# SparkIO_Thermal_Shield.net
KiCad netlist of a schematic drawn in Altium Designer
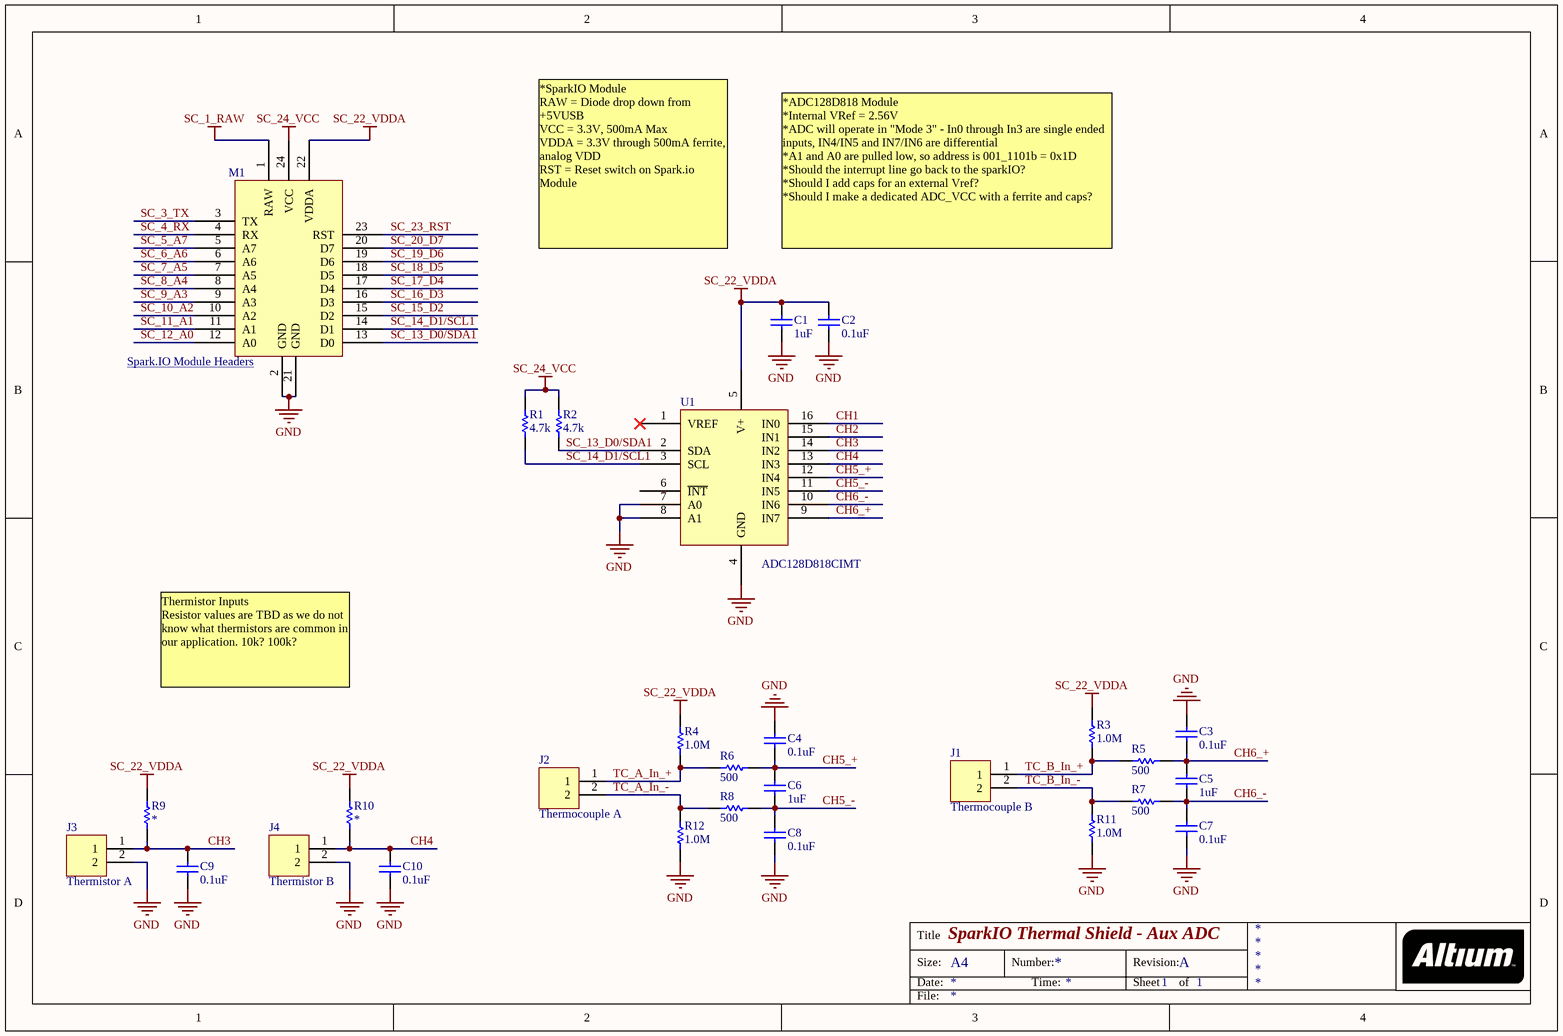
[diagram p0: SparkIO Thermal Shield.SchDoc]

(export (version "E")
  (design (tool "Eeschema 10.0.6"))
  (components
    (comp (ref "C1")
      (value "1uF")
      (footprint "0603")
      (description "Capacitor")
      (libsource (lib "MakerBot") (part "Capacitor"))
    )
    (comp (ref "C2")
      (value "0.1uF")
      (footprint "0603")
      (description "Capacitor")
      (libsource (lib "MakerBot") (part "Capacitor"))
    )
    (comp (ref "C3")
      (value "0.1uF")
      (footprint "0603")
      (description "Capacitor")
      (libsource (lib "MakerBot") (part "Capacitor"))
    )
    (comp (ref "C4")
      (value "0.1uF")
      (footprint "0603")
      (description "Capacitor")
      (libsource (lib "MakerBot") (part "Capacitor"))
    )
    (comp (ref "C5")
      (value "1uF")
      (footprint "0603")
      (description "Capacitor")
      (libsource (lib "MakerBot") (part "Capacitor"))
    )
    (comp (ref "C6")
      (value "1uF")
      (footprint "0603")
      (description "Capacitor")
      (libsource (lib "MakerBot") (part "Capacitor"))
    )
    (comp (ref "C7")
      (value "0.1uF")
      (footprint "0603")
      (description "Capacitor")
      (libsource (lib "MakerBot") (part "Capacitor"))
    )
    (comp (ref "C8")
      (value "0.1uF")
      (footprint "0603")
      (description "Capacitor")
      (libsource (lib "MakerBot") (part "Capacitor"))
    )
    (comp (ref "C9")
      (value "0.1uF")
      (footprint "0603")
      (description "Capacitor")
      (libsource (lib "MakerBot") (part "Capacitor"))
    )
    (comp (ref "C10")
      (value "0.1uF")
      (footprint "0603")
      (description "Capacitor")
      (libsource (lib "MakerBot") (part "Capacitor"))
    )
    (comp (ref "J1")
      (value "Thermocouple B")
      (footprint "HDR1X2")
      (description "Header .1\" 2 Pos")
      (libsource (lib "MakerBot") (part "Header 2"))
    )
    (comp (ref "J2")
      (value "Thermocouple A")
      (footprint "HDR1X2")
      (description "Header .1\" 2 Pos")
      (libsource (lib "MakerBot") (part "Header 2"))
    )
    (comp (ref "J3")
      (value "Thermistor A")
      (footprint "HDR1X2")
      (description "Header .1\" 2 Pos")
      (libsource (lib "MakerBot") (part "Header 2"))
    )
    (comp (ref "J4")
      (value "Thermistor B")
      (footprint "HDR1X2")
      (description "Header .1\" 2 Pos")
      (libsource (lib "MakerBot") (part "Header 2"))
    )
    (comp (ref "M1")
      (value "Spark.IO Module Headers")
      (description "SparkIO Module Interface Headers")
      (libsource (lib "MakerBot") (part "SparkIO Module Interface"))
    )
    (comp (ref "R1")
      (value "4.7k")
      (footprint "0603")
      (description "Resistor")
      (libsource (lib "MakerBot") (part "Resistor"))
    )
    (comp (ref "R2")
      (value "4.7k")
      (footprint "0603")
      (description "Resistor")
      (libsource (lib "MakerBot") (part "Resistor"))
    )
    (comp (ref "R3")
      (value "1.0M")
      (footprint "0603")
      (description "Resistor")
      (libsource (lib "MakerBot") (part "Resistor"))
    )
    (comp (ref "R4")
      (value "1.0M")
      (footprint "0603")
      (description "Resistor")
      (libsource (lib "MakerBot") (part "Resistor"))
    )
    (comp (ref "R5")
      (value "500")
      (footprint "0603")
      (description "Resistor")
      (libsource (lib "MakerBot") (part "Resistor"))
    )
    (comp (ref "R6")
      (value "500")
      (footprint "0603")
      (description "Resistor")
      (libsource (lib "MakerBot") (part "Resistor"))
    )
    (comp (ref "R7")
      (value "500")
      (footprint "0603")
      (description "Resistor")
      (libsource (lib "MakerBot") (part "Resistor"))
    )
    (comp (ref "R8")
      (value "500")
      (footprint "0603")
      (description "Resistor")
      (libsource (lib "MakerBot") (part "Resistor"))
    )
    (comp (ref "R9")
      (value "Resistor")
      (footprint "0603")
      (fields (field (name "ALTIUM_VALUE") "*"))
      (libsource (lib "MakerBot") (part "Resistor"))
    )
    (comp (ref "R10")
      (value "Resistor")
      (footprint "0603")
      (fields (field (name "ALTIUM_VALUE") "*"))
      (libsource (lib "MakerBot") (part "Resistor"))
    )
    (comp (ref "R11")
      (value "1.0M")
      (footprint "0603")
      (description "Resistor")
      (libsource (lib "MakerBot") (part "Resistor"))
    )
    (comp (ref "R12")
      (value "1.0M")
      (footprint "0603")
      (description "Resistor")
      (libsource (lib "MakerBot") (part "Resistor"))
    )
    (comp (ref "U1")
      (value "ADC128D818CIMT")
      (footprint "TSSOP16")
      (description "TI ADC128D818CIMT 12bit ADC")
      (libsource (lib "MakerBot") (part "ADC128D818CIMT"))
    )
  )
  (nets
    (net (code "1") (name "/CH1") (class "Default")
      (node (ref "U1") (pin "16") (pinfunction "IN0_16") (pintype "passive"))
    )
    (net (code "2") (name "/CH2") (class "Default")
      (node (ref "U1") (pin "15") (pinfunction "IN1_15") (pintype "passive"))
    )
    (net (code "3") (name "/CH3") (class "Default")
      (node (ref "C9") (pin "1") (pinfunction "1_1") (pintype "passive"))
      (node (ref "J3") (pin "1") (pinfunction "1_1") (pintype "passive"))
      (node (ref "R9") (pin "2") (pinfunction "2_2") (pintype "passive"))
      (node (ref "U1") (pin "14") (pinfunction "IN2_14") (pintype "passive"))
    )
    (net (code "4") (name "/CH4") (class "Default")
      (node (ref "C10") (pin "1") (pinfunction "1_1") (pintype "passive"))
      (node (ref "J4") (pin "1") (pinfunction "1_1") (pintype "passive"))
      (node (ref "R10") (pin "2") (pinfunction "2_2") (pintype "passive"))
      (node (ref "U1") (pin "13") (pinfunction "IN3_13") (pintype "passive"))
    )
    (net (code "5") (name "/CH5_+") (class "Default")
      (node (ref "C4") (pin "2") (pinfunction "2_2") (pintype "passive"))
      (node (ref "C6") (pin "1") (pinfunction "1_1") (pintype "passive"))
      (node (ref "R6") (pin "1") (pinfunction "1_1") (pintype "passive"))
      (node (ref "U1") (pin "12") (pinfunction "IN4_12") (pintype "passive"))
    )
    (net (code "6") (name "/CH5_-") (class "Default")
      (node (ref "C6") (pin "2") (pinfunction "2_2") (pintype "passive"))
      (node (ref "C8") (pin "1") (pinfunction "1_1") (pintype "passive"))
      (node (ref "R8") (pin "1") (pinfunction "1_1") (pintype "passive"))
      (node (ref "U1") (pin "11") (pinfunction "IN5_11") (pintype "passive"))
    )
    (net (code "7") (name "/CH6_+") (class "Default")
      (node (ref "C3") (pin "2") (pinfunction "2_2") (pintype "passive"))
      (node (ref "C5") (pin "1") (pinfunction "1_1") (pintype "passive"))
      (node (ref "R5") (pin "1") (pinfunction "1_1") (pintype "passive"))
      (node (ref "U1") (pin "9") (pinfunction "IN7_9") (pintype "passive"))
    )
    (net (code "8") (name "/CH6_-") (class "Default")
      (node (ref "C5") (pin "2") (pinfunction "2_2") (pintype "passive"))
      (node (ref "C7") (pin "1") (pinfunction "1_1") (pintype "passive"))
      (node (ref "R7") (pin "1") (pinfunction "1_1") (pintype "passive"))
      (node (ref "U1") (pin "10") (pinfunction "IN6_10") (pintype "passive"))
    )
    (net (code "9") (name "/SC_3_TX") (class "Default")
      (node (ref "M1") (pin "3") (pinfunction "TX_3") (pintype "passive"))
    )
    (net (code "10") (name "/SC_4_RX") (class "Default")
      (node (ref "M1") (pin "4") (pinfunction "RX_4") (pintype "passive"))
    )
    (net (code "11") (name "/SC_5_A7") (class "Default")
      (node (ref "M1") (pin "5") (pinfunction "A7_5") (pintype "passive"))
    )
    (net (code "12") (name "/SC_6_A6") (class "Default")
      (node (ref "M1") (pin "6") (pinfunction "A6_6") (pintype "passive"))
    )
    (net (code "13") (name "/SC_7_A5") (class "Default")
      (node (ref "M1") (pin "7") (pinfunction "A5_7") (pintype "passive"))
    )
    (net (code "14") (name "/SC_8_A4") (class "Default")
      (node (ref "M1") (pin "8") (pinfunction "A4_8") (pintype "passive"))
    )
    (net (code "15") (name "/SC_9_A3") (class "Default")
      (node (ref "M1") (pin "9") (pinfunction "A3_9") (pintype "passive"))
    )
    (net (code "16") (name "/SC_10_A2") (class "Default")
      (node (ref "M1") (pin "10") (pinfunction "A2_10") (pintype "passive"))
    )
    (net (code "17") (name "/SC_11_A1") (class "Default")
      (node (ref "M1") (pin "11") (pinfunction "A1_11") (pintype "passive"))
    )
    (net (code "18") (name "/SC_12_A0") (class "Default")
      (node (ref "M1") (pin "12") (pinfunction "A0_12") (pintype "passive"))
    )
    (net (code "19") (name "/SC_13_D0{slash}SDA1") (class "Default")
      (node (ref "M1") (pin "13") (pinfunction "D0_13") (pintype "passive"))
      (node (ref "R2") (pin "2") (pinfunction "2_2") (pintype "passive"))
      (node (ref "U1") (pin "2") (pinfunction "SDA_2") (pintype "passive"))
    )
    (net (code "20") (name "/SC_14_D1{slash}SCL1") (class "Default")
      (node (ref "M1") (pin "14") (pinfunction "D1_14") (pintype "passive"))
      (node (ref "R1") (pin "2") (pinfunction "2_2") (pintype "passive"))
      (node (ref "U1") (pin "3") (pinfunction "SCL_3") (pintype "passive"))
    )
    (net (code "21") (name "/SC_15_D2") (class "Default")
      (node (ref "M1") (pin "15") (pinfunction "D2_15") (pintype "passive"))
    )
    (net (code "22") (name "/SC_16_D3") (class "Default")
      (node (ref "M1") (pin "16") (pinfunction "D3_16") (pintype "passive"))
    )
    (net (code "23") (name "/SC_17_D4") (class "Default")
      (node (ref "M1") (pin "17") (pinfunction "D4_17") (pintype "passive"))
    )
    (net (code "24") (name "/SC_18_D5") (class "Default")
      (node (ref "M1") (pin "18") (pinfunction "D5_18") (pintype "passive"))
    )
    (net (code "25") (name "/SC_19_D6") (class "Default")
      (node (ref "M1") (pin "19") (pinfunction "D6_19") (pintype "passive"))
    )
    (net (code "26") (name "/SC_20_D7") (class "Default")
      (node (ref "M1") (pin "20") (pinfunction "D7_20") (pintype "passive"))
    )
    (net (code "27") (name "/SC_23_RST") (class "Default")
      (node (ref "M1") (pin "23") (pinfunction "RST_23") (pintype "passive"))
    )
    (net (code "28") (name "/TC_A_In_+") (class "Default")
      (node (ref "J2") (pin "1") (pinfunction "1_1") (pintype "passive"))
      (node (ref "R4") (pin "2") (pinfunction "2_2") (pintype "passive"))
      (node (ref "R6") (pin "2") (pinfunction "2_2") (pintype "passive"))
    )
    (net (code "29") (name "/TC_A_In_-") (class "Default")
      (node (ref "J2") (pin "2") (pinfunction "2_2") (pintype "passive"))
      (node (ref "R12") (pin "1") (pinfunction "1_1") (pintype "passive"))
      (node (ref "R8") (pin "2") (pinfunction "2_2") (pintype "passive"))
    )
    (net (code "30") (name "/TC_B_In_+") (class "Default")
      (node (ref "J1") (pin "1") (pinfunction "1_1") (pintype "passive"))
      (node (ref "R3") (pin "2") (pinfunction "2_2") (pintype "passive"))
      (node (ref "R5") (pin "2") (pinfunction "2_2") (pintype "passive"))
    )
    (net (code "31") (name "/TC_B_In_-") (class "Default")
      (node (ref "J1") (pin "2") (pinfunction "2_2") (pintype "passive"))
      (node (ref "R11") (pin "1") (pinfunction "1_1") (pintype "passive"))
      (node (ref "R7") (pin "2") (pinfunction "2_2") (pintype "passive"))
    )
    (net (code "32") (name "GND") (class "Default")
      (node (ref "C1") (pin "2") (pinfunction "2_2") (pintype "passive"))
      (node (ref "C10") (pin "2") (pinfunction "2_2") (pintype "passive"))
      (node (ref "C2") (pin "2") (pinfunction "2_2") (pintype "passive"))
      (node (ref "C3") (pin "1") (pinfunction "1_1") (pintype "passive"))
      (node (ref "C4") (pin "1") (pinfunction "1_1") (pintype "passive"))
      (node (ref "C7") (pin "2") (pinfunction "2_2") (pintype "passive"))
      (node (ref "C8") (pin "2") (pinfunction "2_2") (pintype "passive"))
      (node (ref "C9") (pin "2") (pinfunction "2_2") (pintype "passive"))
      (node (ref "J3") (pin "2") (pinfunction "2_2") (pintype "passive"))
      (node (ref "J4") (pin "2") (pinfunction "2_2") (pintype "passive"))
      (node (ref "M1") (pin "2") (pinfunction "GND_2") (pintype "passive"))
      (node (ref "M1") (pin "21") (pinfunction "GND_21") (pintype "passive"))
      (node (ref "R11") (pin "2") (pinfunction "2_2") (pintype "passive"))
      (node (ref "R12") (pin "2") (pinfunction "2_2") (pintype "passive"))
      (node (ref "U1") (pin "4") (pinfunction "GND_4") (pintype "passive"))
      (node (ref "U1") (pin "7") (pinfunction "A0_7") (pintype "passive"))
      (node (ref "U1") (pin "8") (pinfunction "A1_8") (pintype "passive"))
    )
    (net (code "33") (name "SC_1_RAW") (class "Default")
      (node (ref "M1") (pin "1") (pinfunction "RAW_1") (pintype "passive"))
    )
    (net (code "34") (name "SC_22_VDDA") (class "Default")
      (node (ref "C1") (pin "1") (pinfunction "1_1") (pintype "passive"))
      (node (ref "C2") (pin "1") (pinfunction "1_1") (pintype "passive"))
      (node (ref "M1") (pin "22") (pinfunction "VDDA_22") (pintype "passive"))
      (node (ref "R10") (pin "1") (pinfunction "1_1") (pintype "passive"))
      (node (ref "R3") (pin "1") (pinfunction "1_1") (pintype "passive"))
      (node (ref "R4") (pin "1") (pinfunction "1_1") (pintype "passive"))
      (node (ref "R9") (pin "1") (pinfunction "1_1") (pintype "passive"))
      (node (ref "U1") (pin "5") (pinfunction "V+_5") (pintype "passive"))
    )
    (net (code "35") (name "SC_24_VCC") (class "Default")
      (node (ref "M1") (pin "24") (pinfunction "VCC_24") (pintype "passive"))
      (node (ref "R1") (pin "1") (pinfunction "1_1") (pintype "passive"))
      (node (ref "R2") (pin "1") (pinfunction "1_1") (pintype "passive"))
    )
    (net (code "36") (name "unconnected-(U1-VREF-Pad1)") (class "Default")
      (node (ref "U1") (pin "1") (pinfunction "VREF_1") (pintype "passive+no_connect"))
    )
    (net (code "37") (name "unconnected-(U1-~{INT}-Pad6)") (class "Default")
      (node (ref "U1") (pin "6") (pinfunction "~{INT}_6") (pintype "passive"))
    )
  )
)
